# Display.net
KiCad netlist of a schematic drawn in Altium Designer
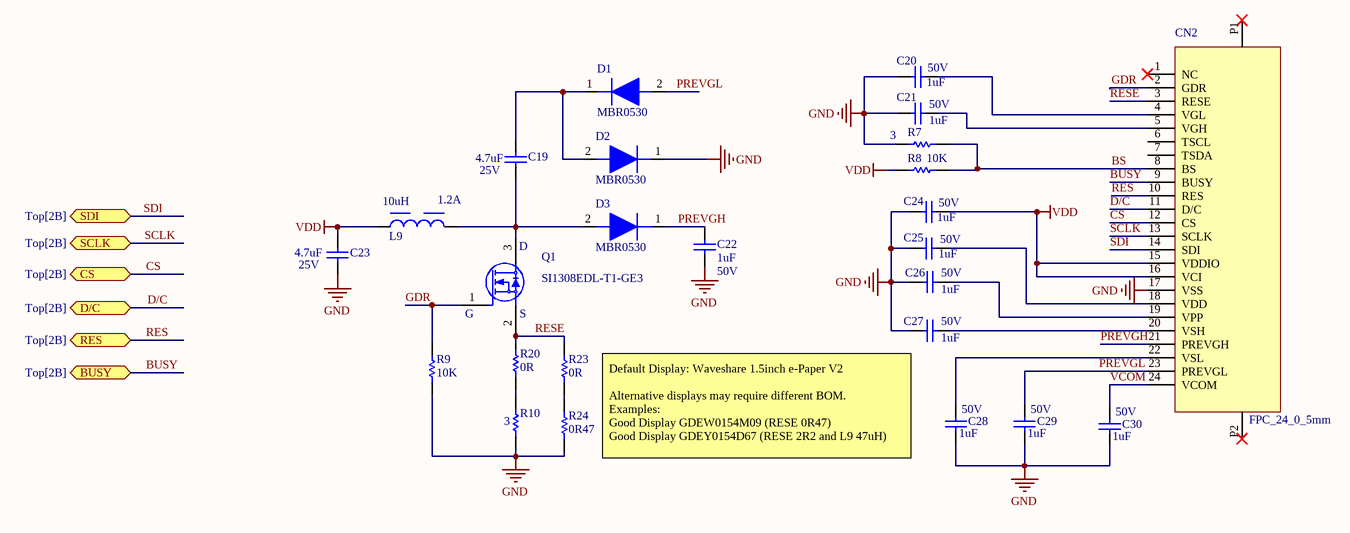
[diagram p0: Display.SchDoc]

(export (version "E")
  (design (tool "Eeschema 10.0.6"))
  (components
    (comp (ref "C19")
      (value "4.7uF")
      (footprint "C0603")
      (description "CAP CER 4.7UF 25V X6S 0603")
      (fields
        (field (name "MANUFACTURER") "Murata")
        (field (name "MANUFACTURER PART NUMBER") "GRM188C81E475KE11D")
        (field (name "VOLTAGE") "25V")
      )
      (libsource (lib "MCD_PARTS_database") (part "Capacitor"))
    )
    (comp (ref "C20")
      (value "1uF")
      (footprint "C0603_H0P8")
      (description "Multilayer Ceramic Capacitor, 1 uF, 50 V, ± 10%, X5R, 0603 [1608 Metric]")
      (fields
        (field (name "MANUFACTURER") "Murata")
        (field (name "MANUFACTURER PART NUMBER") "GRT188R61H105KE13D")
        (field (name "VOLTAGE RATING") "50V")
      )
      (libsource (lib "MCD_PARTS_database") (part "Capacitor"))
    )
    (comp (ref "C21")
      (value "1uF")
      (footprint "C0603_H0P8")
      (description "Multilayer Ceramic Capacitor, 1 uF, 50 V, ± 10%, X5R, 0603 [1608 Metric]")
      (fields
        (field (name "MANUFACTURER") "Murata")
        (field (name "MANUFACTURER PART NUMBER") "GRT188R61H105KE13D")
        (field (name "VOLTAGE RATING") "50V")
      )
      (libsource (lib "MCD_PARTS_database") (part "Capacitor"))
    )
    (comp (ref "C22")
      (value "1uF")
      (footprint "C0603_H0P8")
      (description "Multilayer Ceramic Capacitor, 1 uF, 50 V, ± 10%, X5R, 0603 [1608 Metric]")
      (fields
        (field (name "MANUFACTURER") "Murata")
        (field (name "MANUFACTURER PART NUMBER") "GRT188R61H105KE13D")
        (field (name "VOLTAGE RATING") "50V")
      )
      (libsource (lib "MCD_PARTS_database") (part "Capacitor"))
    )
    (comp (ref "C23")
      (value "4.7uF")
      (footprint "C0603")
      (description "CAP CER 4.7UF 25V X6S 0603")
      (fields
        (field (name "MANUFACTURER") "Murata")
        (field (name "MANUFACTURER PART NUMBER") "GRM188C81E475KE11D")
        (field (name "VOLTAGE") "25V")
      )
      (libsource (lib "MCD_PARTS_database") (part "Capacitor"))
    )
    (comp (ref "C24")
      (value "1uF")
      (footprint "C0603_H0P8")
      (description "Multilayer Ceramic Capacitor, 1 uF, 50 V, ± 10%, X5R, 0603 [1608 Metric]")
      (fields
        (field (name "MANUFACTURER") "Murata")
        (field (name "MANUFACTURER PART NUMBER") "GRT188R61H105KE13D")
        (field (name "VOLTAGE RATING") "50V")
      )
      (libsource (lib "MCD_PARTS_database") (part "Capacitor"))
    )
    (comp (ref "C25")
      (value "1uF")
      (footprint "C0603_H0P8")
      (description "Multilayer Ceramic Capacitor, 1 uF, 50 V, ± 10%, X5R, 0603 [1608 Metric]")
      (fields
        (field (name "MANUFACTURER") "Murata")
        (field (name "MANUFACTURER PART NUMBER") "GRT188R61H105KE13D")
        (field (name "VOLTAGE RATING") "50V")
      )
      (libsource (lib "MCD_PARTS_database") (part "Capacitor"))
    )
    (comp (ref "C26")
      (value "1uF")
      (footprint "C0603_H0P8")
      (description "Multilayer Ceramic Capacitor, 1 uF, 50 V, ± 10%, X5R, 0603 [1608 Metric]")
      (fields
        (field (name "MANUFACTURER") "Murata")
        (field (name "MANUFACTURER PART NUMBER") "GRT188R61H105KE13D")
        (field (name "VOLTAGE RATING") "50V")
      )
      (libsource (lib "MCD_PARTS_database") (part "Capacitor"))
    )
    (comp (ref "C27")
      (value "1uF")
      (footprint "C0603_H0P8")
      (description "Multilayer Ceramic Capacitor, 1 uF, 50 V, ± 10%, X5R, 0603 [1608 Metric]")
      (fields
        (field (name "MANUFACTURER") "Murata")
        (field (name "MANUFACTURER PART NUMBER") "GRT188R61H105KE13D")
        (field (name "VOLTAGE RATING") "50V")
      )
      (libsource (lib "MCD_PARTS_database") (part "Capacitor"))
    )
    (comp (ref "C28")
      (value "1uF")
      (footprint "C0603_H0P8")
      (description "Multilayer Ceramic Capacitor, 1 uF, 50 V, ± 10%, X5R, 0603 [1608 Metric]")
      (fields
        (field (name "MANUFACTURER") "Murata")
        (field (name "MANUFACTURER PART NUMBER") "GRT188R61H105KE13D")
        (field (name "VOLTAGE RATING") "50V")
      )
      (libsource (lib "MCD_PARTS_database") (part "Capacitor"))
    )
    (comp (ref "C29")
      (value "1uF")
      (footprint "C0603_H0P8")
      (description "Multilayer Ceramic Capacitor, 1 uF, 50 V, ± 10%, X5R, 0603 [1608 Metric]")
      (fields
        (field (name "MANUFACTURER") "Murata")
        (field (name "MANUFACTURER PART NUMBER") "GRT188R61H105KE13D")
        (field (name "VOLTAGE RATING") "50V")
      )
      (libsource (lib "MCD_PARTS_database") (part "Capacitor"))
    )
    (comp (ref "C30")
      (value "1uF")
      (footprint "C0603_H0P8")
      (description "Multilayer Ceramic Capacitor, 1 uF, 50 V, ± 10%, X5R, 0603 [1608 Metric]")
      (fields
        (field (name "MANUFACTURER") "Murata")
        (field (name "MANUFACTURER PART NUMBER") "GRT188R61H105KE13D")
        (field (name "VOLTAGE RATING") "50V")
      )
      (libsource (lib "MCD_PARTS_database") (part "Capacitor"))
    )
    (comp (ref "CN2")
      (value "FPC_24_0_5mm")
      (footprint "CON_5034802400_MOL")
      (description "Conn, Ffc/fpc, R/a, 24Pos, 1Row, 0.5Mm Rohs Compliant: Yes")
      (fields (field (name "MANUFACTURER") "Molex") (field (name "MANUFACTURER PART NUMBER") "503480-2400"))
      (libsource (lib "STEVAL-ESLBLECB") (part "FPC_24_0_5mm"))
    )
    (comp (ref "D1")
      (value "MBR0530")
      (footprint "SOD3716X135N")
      (description "Diode, Schottky Barrier, Vr 30V, If 0.5A, Pkg SOD-123, Vf 0.43V, Tj +125degc, Cs 5.5A")
      (fields
        (field (name "MANUFACTURER") "ON Semiconductor / Fairchild")
        (field (name "MANUFACTURER PART NUMBER") "MBR0530T1G")
      )
      (libsource (lib "STEVAL-ESLBLECB") (part "MBR0530"))
    )
    (comp (ref "D2")
      (value "MBR0530")
      (footprint "SOD3716X135N")
      (description "Diode, Schottky Barrier, Vr 30V, If 0.5A, Pkg SOD-123, Vf 0.43V, Tj +125degc, Cs 5.5A")
      (fields
        (field (name "MANUFACTURER") "ON Semiconductor / Fairchild")
        (field (name "MANUFACTURER PART NUMBER") "MBR0530T1G")
      )
      (libsource (lib "STEVAL-ESLBLECB") (part "MBR0530"))
    )
    (comp (ref "D3")
      (value "MBR0530")
      (footprint "SOD3716X135N")
      (description "Diode, Schottky Barrier, Vr 30V, If 0.5A, Pkg SOD-123, Vf 0.43V, Tj +125degc, Cs 5.5A")
      (fields
        (field (name "MANUFACTURER") "ON Semiconductor / Fairchild")
        (field (name "MANUFACTURER PART NUMBER") "MBR0530T1G")
      )
      (libsource (lib "STEVAL-ESLBLECB") (part "MBR0530"))
    )
    (comp (ref "L9")
      (value "10uH, 1.2A")
      (footprint "WE-LQS_4018")
      (description "WE-LQS SMT Power Inductor, size 4018, 10uH, 1.2A, 0.15Ohm")
      (fields
        (field (name "MANUFACTURER PART NUMBER") "74404042100")
        (field (name "MANUFACTURER") "Wurth Elektronik")
        (field (name "INDUCTANCE") "10uH")
        (field (name "RATED CURRENT") "1.2A")
      )
      (libsource (lib "STEVAL-ESLBLECB") (part "74404042100"))
    )
    (comp (ref "Q1")
      (value "SI1308EDL-T1-GE3")
      (footprint "MOS_SOT323-3L")
      (description "Transistor, MOSFET, N-CH, 30V, 1.4A, SOT-323")
      (fields (field (name "INTERNAL_PART_NUMBER") "MCD-02504") (field (name "MANUFACTURER") "VISHAY"))
      (libsource (lib "STEVAL-ESLBLECB") (part "SI1308EDL"))
    )
    (comp (ref "R7")
      (value "3")
      (footprint "R0402")
      (description "Res Thick Film 0402 3 Ohm 1% 1/16W ±200ppm/°C Molded SMD Paper T/R")
      (fields
        (field (name "MANUFACTURER") "Yageo")
        (field (name "MANUFACTURER PART NUMBER") "RC0402FR-073RL")
      )
      (libsource (lib "MCD_PARTS_database") (part "Resistor"))
    )
    (comp (ref "R8")
      (value "10K")
      (footprint "R0402")
      (description "Resistor, 10K, 0402, +/-0.1%, 1/16W, +/-25ppm/°C")
      (fields (field (name "INTERNAL_PART_NUMBER") "MCD-02551") (field (name "MANUFACTURER") "YAGEO"))
      (libsource (lib "MCD_PARTS_database") (part "Resistor"))
    )
    (comp (ref "R9")
      (value "10K")
      (footprint "R0402")
      (description "Resistor, 10K, 0402, +/-0.1%, 1/16W, +/-25ppm/°C")
      (fields (field (name "INTERNAL_PART_NUMBER") "MCD-02551") (field (name "MANUFACTURER") "YAGEO"))
      (libsource (lib "MCD_PARTS_database") (part "Resistor"))
    )
    (comp (ref "R10")
      (value "3")
      (footprint "R0402")
      (description "Res Thick Film 0402 3 Ohm 1% 1/16W ±200ppm/°C Molded SMD Paper T/R")
      (fields
        (field (name "MANUFACTURER") "Yageo")
        (field (name "MANUFACTURER PART NUMBER") "RC0402FR-073RL")
      )
      (libsource (lib "MCD_PARTS_database") (part "Resistor"))
    )
    (comp (ref "R20")
      (value "0R")
      (footprint "R0402")
      (description "Resistor, 0R, 0402, +/-5%, 1/16W")
      (fields (field (name "INTERNAL_PART_NUMBER") "MCD-00052") (field (name "MANUFACTURER") "YAGEO"))
      (libsource (lib "MCD_PARTS_database") (part "Resistor"))
    )
    (comp (ref "R23")
      (value "0R")
      (footprint "R0402")
      (description "Resistor, 0R, 0402, +/-5%, 1/16W")
      (fields (field (name "INTERNAL_PART_NUMBER") "MCD-00052") (field (name "MANUFACTURER") "YAGEO"))
      (libsource (lib "MCD_PARTS_database") (part "Resistor"))
    )
    (comp (ref "R24")
      (value "0R47")
      (footprint "R0402")
      (description "Resistor, 0R47, 0402, +/-1%, 1/16W")
      (fields (field (name "INTERNAL_PART_NUMBER") "MCD-02517") (field (name "MANUFACTURER") "YAGEO"))
      (libsource (lib "MCD_PARTS_database") (part "Resistor"))
    )
  )
  (nets
    (net (code "1") (name "/BS") (class "Default")
      (node (ref "CN2") (pin "8") (pinfunction "BS_8") (pintype "passive"))
      (node (ref "R7") (pin "1") (pinfunction "1_1") (pintype "passive"))
      (node (ref "R8") (pin "2") (pinfunction "2_2") (pintype "passive"))
    )
    (net (code "2") (name "/BUSY") (class "Default")
      (node (ref "CN2") (pin "9") (pinfunction "BUSY_9") (pintype "passive"))
    )
    (net (code "3") (name "/CS") (class "Default")
      (node (ref "CN2") (pin "12") (pinfunction "CS_12") (pintype "passive"))
    )
    (net (code "4") (name "/D{slash}C") (class "Default")
      (node (ref "CN2") (pin "11") (pinfunction "D/C_11") (pintype "passive"))
    )
    (net (code "5") (name "/GDR") (class "Default")
      (node (ref "CN2") (pin "2") (pinfunction "GDR_2") (pintype "passive"))
      (node (ref "Q1") (pin "1") (pinfunction "G_1") (pintype "passive"))
      (node (ref "R9") (pin "2") (pinfunction "2_2") (pintype "passive"))
    )
    (net (code "6") (name "/PREVGH") (class "Default")
      (node (ref "C22") (pin "2") (pinfunction "2_2") (pintype "passive"))
      (node (ref "CN2") (pin "21") (pinfunction "PREVGH_21") (pintype "passive"))
      (node (ref "D3") (pin "1") (pinfunction "1_1") (pintype "passive"))
    )
    (net (code "7") (name "/PREVGL") (class "Default")
      (node (ref "C29") (pin "2") (pinfunction "2_2") (pintype "passive"))
      (node (ref "CN2") (pin "23") (pinfunction "PREVGL_23") (pintype "passive"))
      (node (ref "D1") (pin "2") (pinfunction "2_2") (pintype "passive"))
    )
    (net (code "8") (name "/RES") (class "Default")
      (node (ref "CN2") (pin "10") (pinfunction "RES_10") (pintype "passive"))
    )
    (net (code "9") (name "/RESE") (class "Default")
      (node (ref "CN2") (pin "3") (pinfunction "RESE_3") (pintype "passive"))
      (node (ref "Q1") (pin "2") (pinfunction "S_2") (pintype "passive"))
      (node (ref "R20") (pin "2") (pinfunction "2_2") (pintype "passive"))
      (node (ref "R23") (pin "2") (pinfunction "2_2") (pintype "passive"))
    )
    (net (code "10") (name "/SCLK") (class "Default")
      (node (ref "CN2") (pin "13") (pinfunction "SCLK_13") (pintype "passive"))
    )
    (net (code "11") (name "/SDI") (class "Default")
      (node (ref "CN2") (pin "14") (pinfunction "SDI_14") (pintype "passive"))
    )
    (net (code "12") (name "/VCOM") (class "Default")
      (node (ref "C30") (pin "2") (pinfunction "2_2") (pintype "passive"))
      (node (ref "CN2") (pin "24") (pinfunction "VCOM_24") (pintype "passive"))
    )
    (net (code "13") (name "GND") (class "Default")
      (node (ref "C20") (pin "1") (pinfunction "1_1") (pintype "passive"))
      (node (ref "C21") (pin "1") (pinfunction "1_1") (pintype "passive"))
      (node (ref "C22") (pin "1") (pinfunction "1_1") (pintype "passive"))
      (node (ref "C23") (pin "1") (pinfunction "1_1") (pintype "passive"))
      (node (ref "C24") (pin "1") (pinfunction "1_1") (pintype "passive"))
      (node (ref "C25") (pin "1") (pinfunction "1_1") (pintype "passive"))
      (node (ref "C26") (pin "1") (pinfunction "1_1") (pintype "passive"))
      (node (ref "C27") (pin "1") (pinfunction "1_1") (pintype "passive"))
      (node (ref "C28") (pin "1") (pinfunction "1_1") (pintype "passive"))
      (node (ref "C29") (pin "1") (pinfunction "1_1") (pintype "passive"))
      (node (ref "C30") (pin "1") (pinfunction "1_1") (pintype "passive"))
      (node (ref "CN2") (pin "17") (pinfunction "VSS_17") (pintype "passive"))
      (node (ref "D2") (pin "1") (pinfunction "1_1") (pintype "passive"))
      (node (ref "R10") (pin "1") (pinfunction "1_1") (pintype "passive"))
      (node (ref "R24") (pin "2") (pinfunction "2_2") (pintype "passive"))
      (node (ref "R7") (pin "2") (pinfunction "2_2") (pintype "passive"))
      (node (ref "R9") (pin "1") (pinfunction "1_1") (pintype "passive"))
    )
    (net (code "14") (name "Net-(C19-Pad2)") (class "Default")
      (node (ref "C19") (pin "2") (pinfunction "2_2") (pintype "passive"))
      (node (ref "D1") (pin "1") (pinfunction "1_1") (pintype "passive"))
      (node (ref "D2") (pin "2") (pinfunction "2_2") (pintype "passive"))
    )
    (net (code "15") (name "Net-(CN2-VDD)") (class "Default")
      (node (ref "C25") (pin "2") (pinfunction "2_2") (pintype "passive"))
      (node (ref "CN2") (pin "18") (pinfunction "VDD_18") (pintype "passive"))
    )
    (net (code "16") (name "Net-(CN2-VGH)") (class "Default")
      (node (ref "C21") (pin "2") (pinfunction "2_2") (pintype "passive"))
      (node (ref "CN2") (pin "5") (pinfunction "VGH_5") (pintype "passive"))
    )
    (net (code "17") (name "Net-(CN2-VGL)") (class "Default")
      (node (ref "C20") (pin "2") (pinfunction "2_2") (pintype "passive"))
      (node (ref "CN2") (pin "4") (pinfunction "VGL_4") (pintype "passive"))
    )
    (net (code "18") (name "Net-(CN2-VPP)") (class "Default")
      (node (ref "C26") (pin "2") (pinfunction "2_2") (pintype "passive"))
      (node (ref "CN2") (pin "19") (pinfunction "VPP_19") (pintype "passive"))
    )
    (net (code "19") (name "Net-(CN2-VSH)") (class "Default")
      (node (ref "C27") (pin "2") (pinfunction "2_2") (pintype "passive"))
      (node (ref "CN2") (pin "20") (pinfunction "VSH_20") (pintype "passive"))
    )
    (net (code "20") (name "Net-(CN2-VSL)") (class "Default")
      (node (ref "C28") (pin "2") (pinfunction "2_2") (pintype "passive"))
      (node (ref "CN2") (pin "22") (pinfunction "VSL_22") (pintype "passive"))
    )
    (net (code "21") (name "Net-(Q1-D)") (class "Default")
      (node (ref "C19") (pin "1") (pinfunction "1_1") (pintype "passive"))
      (node (ref "D3") (pin "2") (pinfunction "2_2") (pintype "passive"))
      (node (ref "L9") (pin "2") (pinfunction "2_2") (pintype "passive"))
      (node (ref "Q1") (pin "3") (pinfunction "D_3") (pintype "passive"))
    )
    (net (code "22") (name "Net-(R10-Pad2)") (class "Default")
      (node (ref "R10") (pin "2") (pinfunction "2_2") (pintype "passive"))
      (node (ref "R20") (pin "1") (pinfunction "1_1") (pintype "passive"))
    )
    (net (code "23") (name "Net-(R23-Pad1)") (class "Default")
      (node (ref "R23") (pin "1") (pinfunction "1_1") (pintype "passive"))
      (node (ref "R24") (pin "1") (pinfunction "1_1") (pintype "passive"))
    )
    (net (code "24") (name "VDD") (class "Default")
      (node (ref "C23") (pin "2") (pinfunction "2_2") (pintype "passive"))
      (node (ref "C24") (pin "2") (pinfunction "2_2") (pintype "passive"))
      (node (ref "CN2") (pin "15") (pinfunction "VDDIO_15") (pintype "passive"))
      (node (ref "CN2") (pin "16") (pinfunction "VCI_16") (pintype "passive"))
      (node (ref "L9") (pin "1") (pinfunction "1_1") (pintype "passive"))
      (node (ref "R8") (pin "1") (pinfunction "1_1") (pintype "passive"))
    )
    (net (code "25") (name "unconnected-(CN2-NC-Pad1)") (class "Default")
      (node (ref "CN2") (pin "1") (pinfunction "NC_1") (pintype "passive+no_connect"))
    )
    (net (code "26") (name "unconnected-(CN2-NC-PadP1)") (class "Default")
      (node (ref "CN2") (pin "P1") (pinfunction "NC_P1") (pintype "passive+no_connect"))
    )
    (net (code "27") (name "unconnected-(CN2-NC-PadP2)") (class "Default")
      (node (ref "CN2") (pin "P2") (pinfunction "NC_P2") (pintype "passive+no_connect"))
    )
    (net (code "28") (name "unconnected-(CN2-TSCL-Pad6)") (class "Default")
      (node (ref "CN2") (pin "6") (pinfunction "TSCL_6") (pintype "passive"))
    )
    (net (code "29") (name "unconnected-(CN2-TSDA-Pad7)") (class "Default")
      (node (ref "CN2") (pin "7") (pinfunction "TSDA_7") (pintype "passive"))
    )
  )
)
